# OpenBook_Schematic.net
KiCad netlist of a schematic drawn in EAGLE
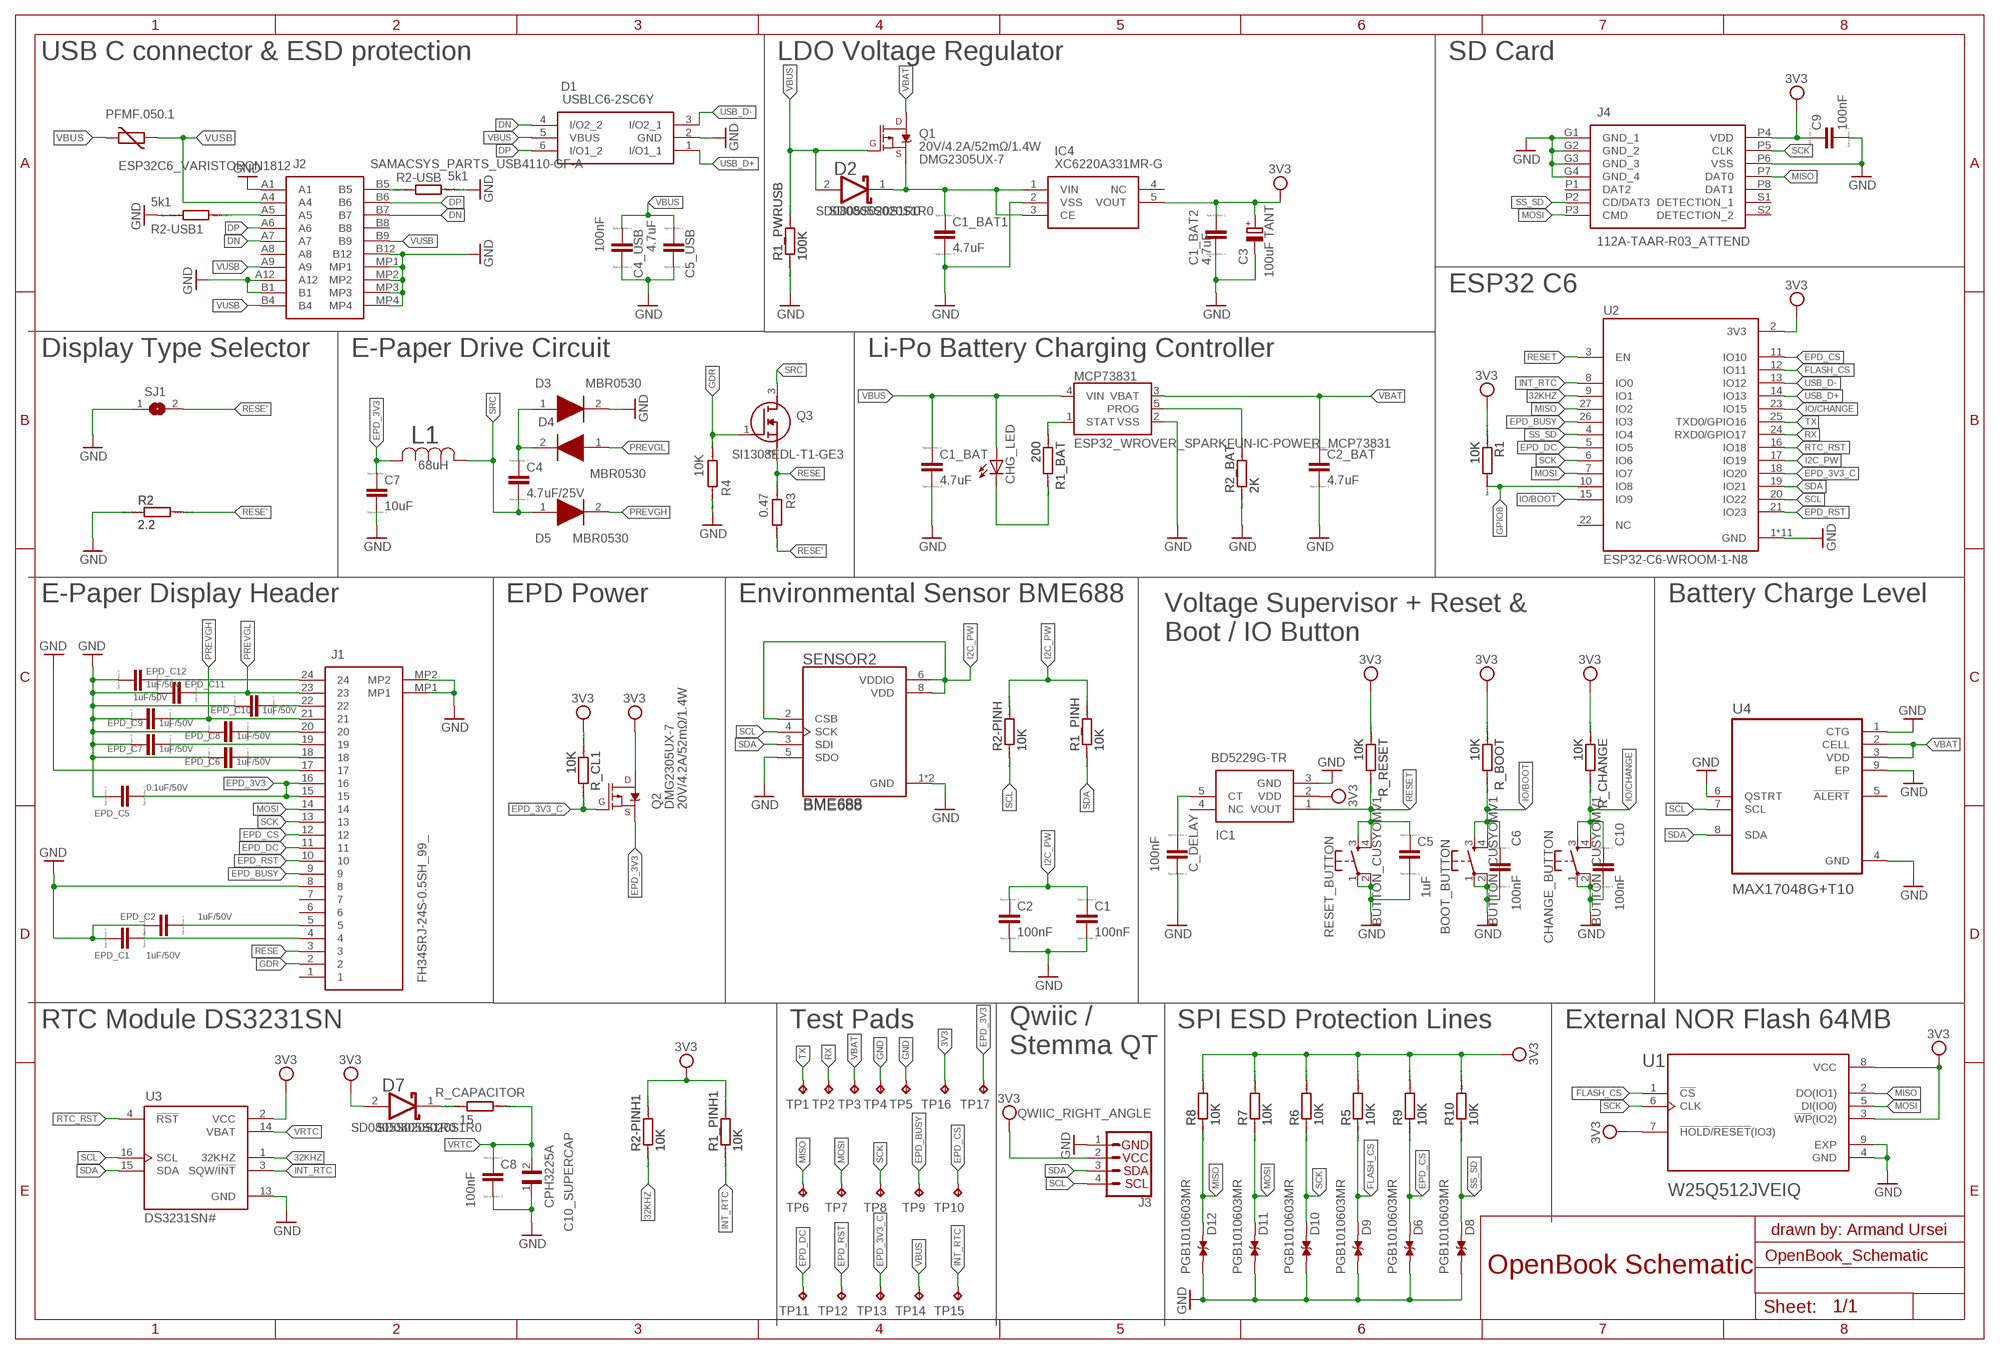
[diagram p0: schematic, sheet 1]

(export (version "E")
  (design (tool "Eeschema 10.0.6"))
  (components
    (comp (ref "BOOT_BUTTON")
      (value "BUTTON_CUSYOMV1")
      (footprint "eagle-import:MYBUTTON")
      (libsource (lib "eagle-import") (part "BUTTON_CUSYOMV1"))
    )
    (comp (ref "C1")
      (value "100nF")
      (footprint "eagle-import:ESP32_WROVER_EAGLE-LTSPICE_C0402")
      (libsource (lib "eagle-import") (part "ESP32_WROVER_EAGLE-LTSPICE_CC0402"))
    )
    (comp (ref "C1_BAT")
      (value "4.7uF")
      (footprint "eagle-import:ESP32_WROVER_EAGLE-LTSPICE_C0402")
      (libsource (lib "eagle-import") (part "ESP32_WROVER_EAGLE-LTSPICE_CC0402"))
    )
    (comp (ref "C1_BAT1")
      (value "4.7uF")
      (footprint "eagle-import:ESP32_WROVER_EAGLE-LTSPICE_C0402")
      (libsource (lib "eagle-import") (part "ESP32_WROVER_EAGLE-LTSPICE_CC0402"))
    )
    (comp (ref "C1_BAT2")
      (value "4.7uF")
      (footprint "eagle-import:ESP32_WROVER_EAGLE-LTSPICE_C0402")
      (libsource (lib "eagle-import") (part "ESP32_WROVER_EAGLE-LTSPICE_CC0402"))
    )
    (comp (ref "C2")
      (value "100nF")
      (footprint "eagle-import:ESP32_WROVER_EAGLE-LTSPICE_C0402")
      (libsource (lib "eagle-import") (part "ESP32_WROVER_EAGLE-LTSPICE_CC0402"))
    )
    (comp (ref "C2_BAT")
      (value "4.7uF")
      (footprint "eagle-import:ESP32_WROVER_EAGLE-LTSPICE_C0402")
      (libsource (lib "eagle-import") (part "ESP32_WROVER_EAGLE-LTSPICE_CC0402"))
    )
    (comp (ref "C3")
      (value "100uF TANT")
      (footprint "eagle-import:RCL_CT3528")
      (libsource (lib "eagle-import") (part "RCL_CPOL-EUCT3528"))
    )
    (comp (ref "C4")
      (value "4.7uF/25V")
      (footprint "eagle-import:ESP32_WROVER_EAGLE-LTSPICE_C0402")
      (libsource (lib "eagle-import") (part "ESP32_WROVER_EAGLE-LTSPICE_CC0402"))
    )
    (comp (ref "C4_USB")
      (value "100nF")
      (footprint "eagle-import:ESP32_WROVER_EAGLE-LTSPICE_C0402")
      (libsource (lib "eagle-import") (part "ESP32_WROVER_EAGLE-LTSPICE_CC0402"))
    )
    (comp (ref "C5")
      (value "1uF")
      (footprint "eagle-import:ESP32_WROVER_EAGLE-LTSPICE_C0402")
      (libsource (lib "eagle-import") (part "ESP32_WROVER_EAGLE-LTSPICE_CC0402"))
    )
    (comp (ref "C5_USB")
      (value "4.7uF")
      (footprint "eagle-import:ESP32_WROVER_EAGLE-LTSPICE_C0402")
      (libsource (lib "eagle-import") (part "ESP32_WROVER_EAGLE-LTSPICE_CC0402"))
    )
    (comp (ref "C6")
      (value "100nF")
      (footprint "eagle-import:ESP32_WROVER_EAGLE-LTSPICE_C0402")
      (libsource (lib "eagle-import") (part "ESP32_WROVER_EAGLE-LTSPICE_CC0402"))
    )
    (comp (ref "C7")
      (value "10uF")
      (footprint "eagle-import:ESP32_WROVER_EAGLE-LTSPICE_C0402")
      (libsource (lib "eagle-import") (part "ESP32_WROVER_EAGLE-LTSPICE_CC0402"))
    )
    (comp (ref "C8")
      (value "100nF")
      (footprint "eagle-import:ESP32_WROVER_EAGLE-LTSPICE_C0402")
      (libsource (lib "eagle-import") (part "ESP32_WROVER_EAGLE-LTSPICE_CC0402"))
    )
    (comp (ref "C9")
      (value "100nF")
      (footprint "eagle-import:ESP32_WROVER_EAGLE-LTSPICE_C0402")
      (libsource (lib "eagle-import") (part "ESP32_WROVER_EAGLE-LTSPICE_CC0402"))
    )
    (comp (ref "C10")
      (value "100nF")
      (footprint "eagle-import:ESP32_WROVER_EAGLE-LTSPICE_C0402")
      (libsource (lib "eagle-import") (part "ESP32_WROVER_EAGLE-LTSPICE_CC0402"))
    )
    (comp (ref "C10_SUPERCAP")
      (value "CPH3225A")
      (footprint "eagle-import:CAPCP3225X100N")
      (fields (field (name "MF") "Seiko Instruments"))
      (libsource (lib "eagle-import") (part "CPH3225A"))
    )
    (comp (ref "CHANGE_BUTTON")
      (value "BUTTON_CUSYOMV1")
      (footprint "eagle-import:MYBUTTON")
      (libsource (lib "eagle-import") (part "BUTTON_CUSYOMV1"))
    )
    (comp (ref "CHG_LED")
      (value "ADAFRUIT_LEDCHIP-LED0603")
      (footprint "eagle-import:ADAFRUIT_CHIP-LED0603")
      (libsource (lib "eagle-import") (part "ADAFRUIT_LEDCHIP-LED0603"))
    )
    (comp (ref "C_DELAY")
      (value "100nF")
      (footprint "eagle-import:ESP32_WROVER_EAGLE-LTSPICE_C0402")
      (libsource (lib "eagle-import") (part "ESP32_WROVER_EAGLE-LTSPICE_CC0402"))
    )
    (comp (ref "D1")
      (value "USBLC6-2SC6Y")
      (footprint "eagle-import:SOT95P280X145-6N")
      (fields (field (name "MF") "STMicroelectronics"))
      (libsource (lib "eagle-import") (part "USBLC6-2SC6Y"))
    )
    (comp (ref "D2")
      (value "SD0805S020S1R0")
      (footprint "eagle-import:ESP32_WROVER_AVX---SD0805S020S1R0_AVX_SD0805S020S1R0_0")
      (fields
        (field (name "DIGIKEY_PART_NUMBER") "478-7800-1-ND")
        (field (name "MF") "AVX")
        (field (name "MOUSER_PART_NUMBER") "581-SD0805S020S1R0")
      )
      (libsource (lib "eagle-import") (part "ESP32_WROVER_AVX---SD0805S020S1R0_AVX_SD0805S020S1R0_0_0AVX_SD0805S020S1R0_0_0"))
    )
    (comp (ref "D3")
      (value "MBR0530")
      (footprint "eagle-import:SOD3716X135N")
      (libsource (lib "eagle-import") (part "MBR0530"))
    )
    (comp (ref "D4")
      (value "MBR0530")
      (footprint "eagle-import:SOD3716X135N")
      (libsource (lib "eagle-import") (part "MBR0530"))
    )
    (comp (ref "D5")
      (value "MBR0530")
      (footprint "eagle-import:SOD3716X135N")
      (libsource (lib "eagle-import") (part "MBR0530"))
    )
    (comp (ref "D6")
      (value "PGB1010603MR")
      (footprint "eagle-import:DIOC1608X36N")
      (libsource (lib "eagle-import") (part "PGB1010603MR"))
    )
    (comp (ref "D7")
      (value "SD0805S020S1R0")
      (footprint "eagle-import:ESP32_WROVER_AVX---SD0805S020S1R0_AVX_SD0805S020S1R0_0")
      (fields
        (field (name "DIGIKEY_PART_NUMBER") "478-7800-1-ND")
        (field (name "MF") "AVX")
        (field (name "MOUSER_PART_NUMBER") "581-SD0805S020S1R0")
      )
      (libsource (lib "eagle-import") (part "ESP32_WROVER_AVX---SD0805S020S1R0_AVX_SD0805S020S1R0_0_0AVX_SD0805S020S1R0_0_0"))
    )
    (comp (ref "D8")
      (value "PGB1010603MR")
      (footprint "eagle-import:DIOC1608X36N")
      (libsource (lib "eagle-import") (part "PGB1010603MR"))
    )
    (comp (ref "D9")
      (value "PGB1010603MR")
      (footprint "eagle-import:DIOC1608X36N")
      (libsource (lib "eagle-import") (part "PGB1010603MR"))
    )
    (comp (ref "D10")
      (value "PGB1010603MR")
      (footprint "eagle-import:DIOC1608X36N")
      (libsource (lib "eagle-import") (part "PGB1010603MR"))
    )
    (comp (ref "D11")
      (value "PGB1010603MR")
      (footprint "eagle-import:DIOC1608X36N")
      (libsource (lib "eagle-import") (part "PGB1010603MR"))
    )
    (comp (ref "D12")
      (value "PGB1010603MR")
      (footprint "eagle-import:DIOC1608X36N")
      (libsource (lib "eagle-import") (part "PGB1010603MR"))
    )
    (comp (ref "EPD_C1")
      (value "1uF/50V")
      (footprint "eagle-import:ESP32_WROVER_EAGLE-LTSPICE_C0402")
      (libsource (lib "eagle-import") (part "ESP32_WROVER_EAGLE-LTSPICE_CC0402"))
    )
    (comp (ref "EPD_C2")
      (value "1uF/50V")
      (footprint "eagle-import:ESP32_WROVER_EAGLE-LTSPICE_C0402")
      (libsource (lib "eagle-import") (part "ESP32_WROVER_EAGLE-LTSPICE_CC0402"))
    )
    (comp (ref "EPD_C5")
      (value "0.1uF/50V")
      (footprint "eagle-import:ESP32_WROVER_EAGLE-LTSPICE_C0402")
      (libsource (lib "eagle-import") (part "ESP32_WROVER_EAGLE-LTSPICE_CC0402"))
    )
    (comp (ref "EPD_C6")
      (value "1uF/50V")
      (footprint "eagle-import:ESP32_WROVER_EAGLE-LTSPICE_C0402")
      (libsource (lib "eagle-import") (part "ESP32_WROVER_EAGLE-LTSPICE_CC0402"))
    )
    (comp (ref "EPD_C7")
      (value "1uF/50V")
      (footprint "eagle-import:ESP32_WROVER_EAGLE-LTSPICE_C0402")
      (libsource (lib "eagle-import") (part "ESP32_WROVER_EAGLE-LTSPICE_CC0402"))
    )
    (comp (ref "EPD_C8")
      (value "1uF/50V")
      (footprint "eagle-import:ESP32_WROVER_EAGLE-LTSPICE_C0402")
      (libsource (lib "eagle-import") (part "ESP32_WROVER_EAGLE-LTSPICE_CC0402"))
    )
    (comp (ref "EPD_C9")
      (value "1uF/50V")
      (footprint "eagle-import:ESP32_WROVER_EAGLE-LTSPICE_C0402")
      (libsource (lib "eagle-import") (part "ESP32_WROVER_EAGLE-LTSPICE_CC0402"))
    )
    (comp (ref "EPD_C10")
      (value "1uF/50V")
      (footprint "eagle-import:ESP32_WROVER_EAGLE-LTSPICE_C0402")
      (libsource (lib "eagle-import") (part "ESP32_WROVER_EAGLE-LTSPICE_CC0402"))
    )
    (comp (ref "EPD_C11")
      (value "1uF/50V")
      (footprint "eagle-import:ESP32_WROVER_EAGLE-LTSPICE_C0402")
      (libsource (lib "eagle-import") (part "ESP32_WROVER_EAGLE-LTSPICE_CC0402"))
    )
    (comp (ref "EPD_C12")
      (value "1uF/50V")
      (footprint "eagle-import:ESP32_WROVER_EAGLE-LTSPICE_C0402")
      (libsource (lib "eagle-import") (part "ESP32_WROVER_EAGLE-LTSPICE_CC0402"))
    )
    (comp (ref "IC1")
      (value "BD5229G-TR")
      (footprint "eagle-import:SOT95P280X125-5N")
      (fields (field (name "MOUSER_PART_NUMBER") "755-BD5229G-TR"))
      (libsource (lib "eagle-import") (part "BD5229G-TR"))
    )
    (comp (ref "IC4")
      (value "XC6220A331MR-G")
      (footprint "eagle-import:SOT95P280X120-5N")
      (fields (field (name "MOUSER_PART_NUMBER") "865-XC6220A331MR-G"))
      (libsource (lib "eagle-import") (part "XC6220A331MR-G"))
    )
    (comp (ref "J1")
      (value "FH34SRJ-24S-0.5SH_99_")
      (footprint "eagle-import:FH34SRJ24S05SH99")
      (fields
        (field (name "MANUFACTURER_PART_NUMBER") "FH34SRJ-24S-0.5SH(99)")
        (field (name "MOUSER_PART_NUMBER") "798-FH34SRJ24S05SH99")
      )
      (libsource (lib "eagle-import") (part "FH34SRJ-24S-0.5SH_99_"))
    )
    (comp (ref "J2")
      (value "SAMACSYS_PARTS_USB4110-GF-A")
      (footprint "eagle-import:SAMACSYS_PARTS_USB4110GFA")
      (fields
        (field (name "MANUFACTURER_PART_NUMBER") "USB4110-GF-A")
        (field (name "MOUSER_PART_NUMBER") "640-USB4110-GF-A")
      )
      (libsource (lib "eagle-import") (part "SAMACSYS_PARTS_USB4110-GF-A"))
    )
    (comp (ref "J3")
      (value "QWIIC_RIGHT_ANGLE")
      (footprint "eagle-import:JST04_1MM_RA")
      (libsource (lib "eagle-import") (part "QWIIC_CONNECTORJS-1MM"))
    )
    (comp (ref "J4")
      (value "112A-TAAR-R03_ATTEND")
      (footprint "eagle-import:112ATAARR03ATTEND")
      (fields (field (name "MANUFACTURER_PART_NUMBER") "112A-TAAR-R03 ATTEND"))
      (libsource (lib "eagle-import") (part "112A-TAAR-R03_ATTEND"))
    )
    (comp (ref "L1")
      (value "68uH")
      (footprint "eagle-import:IND_4828-WE-TPC_WRE")
      (fields
        (field (name "MANUFACTURER_PART_NUMBER") "744043680")
        (field (name "COPYRIGHT") "Copyright (C) 2024 Ultra Librarian. All rights reserved.")
      )
      (libsource (lib "eagle-import") (part "744043680IND_4828-WE-TPC_WRE"))
    )
    (comp (ref "MCP73831")
      (value "ESP32_WROVER_SPARKFUN-IC-POWER_MCP73831")
      (footprint "eagle-import:ESP32_WROVER_SPARKFUN-IC-POWER_SOT23-5")
      (libsource (lib "eagle-import") (part "ESP32_WROVER_SPARKFUN-IC-POWER_MCP73831"))
    )
    (comp (ref "PFMF.050.1")
      (value "ESP32C6_VARISTORCN1812")
      (footprint "eagle-import:ESP32C6_VARISTOR_CT_CN1812")
      (libsource (lib "eagle-import") (part "ESP32C6_VARISTORCN1812"))
    )
    (comp (ref "Q1")
      (value "20V/4.2A/52mΩ/1.4W")
      (footprint "eagle-import:ESP32_WROVER_SPARKFUN-DISCRETESEMI_SOT23-3")
      (libsource (lib "eagle-import") (part "ESP32_WROVER_SPARKFUN-DISCRETESEMI_MOSFET_PCH-DMG2305UX-7"))
    )
    (comp (ref "Q2")
      (value "20V/4.2A/52mΩ/1.4W")
      (footprint "eagle-import:ESP32_WROVER_SPARKFUN-DISCRETESEMI_SOT23-3")
      (libsource (lib "eagle-import") (part "ESP32_WROVER_SPARKFUN-DISCRETESEMI_MOSFET_PCH-DMG2305UX-7"))
    )
    (comp (ref "Q3")
      (value "SI1308EDL-T1-GE3")
      (footprint "eagle-import:SOT65P210X110-3N")
      (fields (field (name "MF") "Vishay Siliconix"))
      (libsource (lib "eagle-import") (part "SI1308EDL-T1-GE3"))
    )
    (comp (ref "R1")
      (value "10K")
      (footprint "eagle-import:ESP32_WROVER_EAGLE-LTSPICE_R0402")
      (libsource (lib "eagle-import") (part "ESP32_WROVER_EAGLE-LTSPICE_RR0402"))
    )
    (comp (ref "R1_BAT")
      (value "200")
      (footprint "eagle-import:ESP32_WROVER_EAGLE-LTSPICE_R0402")
      (libsource (lib "eagle-import") (part "ESP32_WROVER_EAGLE-LTSPICE_RR0402"))
    )
    (comp (ref "R1_PINH")
      (value "10K")
      (footprint "eagle-import:ESP32_WROVER_EAGLE-LTSPICE_R0402")
      (libsource (lib "eagle-import") (part "ESP32_WROVER_EAGLE-LTSPICE_RR0402"))
    )
    (comp (ref "R1_PINH1")
      (value "10K")
      (footprint "eagle-import:ESP32_WROVER_EAGLE-LTSPICE_R0402")
      (libsource (lib "eagle-import") (part "ESP32_WROVER_EAGLE-LTSPICE_RR0402"))
    )
    (comp (ref "R1_PWRUSB")
      (value "100K")
      (footprint "eagle-import:ESP32_WROVER_EAGLE-LTSPICE_R0402")
      (libsource (lib "eagle-import") (part "ESP32_WROVER_EAGLE-LTSPICE_RR0402"))
    )
    (comp (ref "R2")
      (value "2.2")
      (footprint "eagle-import:ESP32_WROVER_EAGLE-LTSPICE_R0402")
      (libsource (lib "eagle-import") (part "ESP32_WROVER_EAGLE-LTSPICE_RR0402"))
    )
    (comp (ref "R2-PINH")
      (value "10K")
      (footprint "eagle-import:ESP32_WROVER_EAGLE-LTSPICE_R0402")
      (libsource (lib "eagle-import") (part "ESP32_WROVER_EAGLE-LTSPICE_RR0402"))
    )
    (comp (ref "R2-PINH1")
      (value "10K")
      (footprint "eagle-import:ESP32_WROVER_EAGLE-LTSPICE_R0402")
      (libsource (lib "eagle-import") (part "ESP32_WROVER_EAGLE-LTSPICE_RR0402"))
    )
    (comp (ref "R2-USB")
      (value "5k1")
      (footprint "eagle-import:ESP32_WROVER_EAGLE-LTSPICE_R0402")
      (libsource (lib "eagle-import") (part "ESP32_WROVER_EAGLE-LTSPICE_RR0402"))
    )
    (comp (ref "R2-USB1")
      (value "5k1")
      (footprint "eagle-import:ESP32_WROVER_EAGLE-LTSPICE_R0402")
      (libsource (lib "eagle-import") (part "ESP32_WROVER_EAGLE-LTSPICE_RR0402"))
    )
    (comp (ref "R2_BAT")
      (value "2K")
      (footprint "eagle-import:ESP32_WROVER_EAGLE-LTSPICE_R0402")
      (libsource (lib "eagle-import") (part "ESP32_WROVER_EAGLE-LTSPICE_RR0402"))
    )
    (comp (ref "R3")
      (value "0.47")
      (footprint "eagle-import:ESP32_WROVER_EAGLE-LTSPICE_R0402")
      (libsource (lib "eagle-import") (part "ESP32_WROVER_EAGLE-LTSPICE_RR0402"))
    )
    (comp (ref "R4")
      (value "10K")
      (footprint "eagle-import:ESP32_WROVER_EAGLE-LTSPICE_R0402")
      (libsource (lib "eagle-import") (part "ESP32_WROVER_EAGLE-LTSPICE_RR0402"))
    )
    (comp (ref "R5")
      (value "10K")
      (footprint "eagle-import:ESP32_WROVER_EAGLE-LTSPICE_R0402")
      (libsource (lib "eagle-import") (part "ESP32_WROVER_EAGLE-LTSPICE_RR0402"))
    )
    (comp (ref "R6")
      (value "10K")
      (footprint "eagle-import:ESP32_WROVER_EAGLE-LTSPICE_R0402")
      (libsource (lib "eagle-import") (part "ESP32_WROVER_EAGLE-LTSPICE_RR0402"))
    )
    (comp (ref "R7")
      (value "10K")
      (footprint "eagle-import:ESP32_WROVER_EAGLE-LTSPICE_R0402")
      (libsource (lib "eagle-import") (part "ESP32_WROVER_EAGLE-LTSPICE_RR0402"))
    )
    (comp (ref "R8")
      (value "10K")
      (footprint "eagle-import:ESP32_WROVER_EAGLE-LTSPICE_R0402")
      (libsource (lib "eagle-import") (part "ESP32_WROVER_EAGLE-LTSPICE_RR0402"))
    )
    (comp (ref "R9")
      (value "10K")
      (footprint "eagle-import:ESP32_WROVER_EAGLE-LTSPICE_R0402")
      (libsource (lib "eagle-import") (part "ESP32_WROVER_EAGLE-LTSPICE_RR0402"))
    )
    (comp (ref "R10")
      (value "10K")
      (footprint "eagle-import:ESP32_WROVER_EAGLE-LTSPICE_R0402")
      (libsource (lib "eagle-import") (part "ESP32_WROVER_EAGLE-LTSPICE_RR0402"))
    )
    (comp (ref "RESET_BUTTON")
      (value "BUTTON_CUSYOMV1")
      (footprint "eagle-import:MYBUTTON")
      (libsource (lib "eagle-import") (part "BUTTON_CUSYOMV1"))
    )
    (comp (ref "R_BOOT")
      (value "10K")
      (footprint "eagle-import:ESP32_WROVER_EAGLE-LTSPICE_R0402")
      (libsource (lib "eagle-import") (part "ESP32_WROVER_EAGLE-LTSPICE_RR0402"))
    )
    (comp (ref "R_CAPACITOR")
      (value "15")
      (footprint "eagle-import:ESP32_WROVER_EAGLE-LTSPICE_R0402")
      (libsource (lib "eagle-import") (part "ESP32_WROVER_EAGLE-LTSPICE_RR0402"))
    )
    (comp (ref "R_CHANGE")
      (value "10K")
      (footprint "eagle-import:ESP32_WROVER_EAGLE-LTSPICE_R0402")
      (libsource (lib "eagle-import") (part "ESP32_WROVER_EAGLE-LTSPICE_RR0402"))
    )
    (comp (ref "R_CL1")
      (value "10K")
      (footprint "eagle-import:ESP32_WROVER_EAGLE-LTSPICE_R0402")
      (libsource (lib "eagle-import") (part "ESP32_WROVER_EAGLE-LTSPICE_RR0402"))
    )
    (comp (ref "R_RESET")
      (value "10K")
      (footprint "eagle-import:ESP32_WROVER_EAGLE-LTSPICE_R0402")
      (libsource (lib "eagle-import") (part "ESP32_WROVER_EAGLE-LTSPICE_RR0402"))
    )
    (comp (ref "SENSOR2")
      (value "BME688")
      (footprint "eagle-import:ESP32_WROVER_BME680_PSON80P300X300X100-8N")
      (fields (field (name "MF") "Bosch Sensortec") (field (name "MP") "BME680"))
      (libsource (lib "eagle-import") (part "ESP32_WROVER_BME680_BME680"))
    )
    (comp (ref "SJ1") (value "SJ") (footprint "eagle-import:SJ") (libsource (lib "eagle-import") (part "SJ")))
    (comp (ref "TP1")
      (value "TPTP20R")
      (footprint "eagle-import:TP20R")
      (libsource (lib "eagle-import") (part "TPTP20R"))
    )
    (comp (ref "TP2")
      (value "TPTP20R")
      (footprint "eagle-import:TP20R")
      (libsource (lib "eagle-import") (part "TPTP20R"))
    )
    (comp (ref "TP3")
      (value "TPTP20R")
      (footprint "eagle-import:TP20R")
      (libsource (lib "eagle-import") (part "TPTP20R"))
    )
    (comp (ref "TP4")
      (value "TPTP20R")
      (footprint "eagle-import:TP20R")
      (libsource (lib "eagle-import") (part "TPTP20R"))
    )
    (comp (ref "TP5")
      (value "TPTP20R")
      (footprint "eagle-import:TP20R")
      (libsource (lib "eagle-import") (part "TPTP20R"))
    )
    (comp (ref "TP6")
      (value "TPTP20R")
      (footprint "eagle-import:TP20R")
      (libsource (lib "eagle-import") (part "TPTP20R"))
    )
    (comp (ref "TP7")
      (value "TPTP20R")
      (footprint "eagle-import:TP20R")
      (libsource (lib "eagle-import") (part "TPTP20R"))
    )
    (comp (ref "TP8")
      (value "TPTP20R")
      (footprint "eagle-import:TP20R")
      (libsource (lib "eagle-import") (part "TPTP20R"))
    )
    (comp (ref "TP9")
      (value "TPTP20R")
      (footprint "eagle-import:TP20R")
      (libsource (lib "eagle-import") (part "TPTP20R"))
    )
    (comp (ref "TP10")
      (value "TPTP20R")
      (footprint "eagle-import:TP20R")
      (libsource (lib "eagle-import") (part "TPTP20R"))
    )
    (comp (ref "TP11")
      (value "TPTP20R")
      (footprint "eagle-import:TP20R")
      (libsource (lib "eagle-import") (part "TPTP20R"))
    )
    (comp (ref "TP12")
      (value "TPTP20R")
      (footprint "eagle-import:TP20R")
      (libsource (lib "eagle-import") (part "TPTP20R"))
    )
    (comp (ref "TP13")
      (value "TPTP20R")
      (footprint "eagle-import:TP20R")
      (libsource (lib "eagle-import") (part "TPTP20R"))
    )
    (comp (ref "TP14")
      (value "TPTP20R")
      (footprint "eagle-import:TP20R")
      (libsource (lib "eagle-import") (part "TPTP20R"))
    )
    (comp (ref "TP15")
      (value "TPTP20R")
      (footprint "eagle-import:TP20R")
      (libsource (lib "eagle-import") (part "TPTP20R"))
    )
    (comp (ref "TP16")
      (value "TPTP20R")
      (footprint "eagle-import:TP20R")
      (libsource (lib "eagle-import") (part "TPTP20R"))
    )
    (comp (ref "TP17")
      (value "TPTP20R")
      (footprint "eagle-import:TP20R")
      (libsource (lib "eagle-import") (part "TPTP20R"))
    )
    (comp (ref "U1")
      (value "W25Q512JVEIQ")
      (footprint "eagle-import:SON127P600X800X80-9N")
      (fields (field (name "MF") "Winbond Electronics"))
      (libsource (lib "eagle-import") (part "W25Q512JVEIQ"))
    )
    (comp (ref "U2")
      (value "ESP32-C6-WROOM-1-N8")
      (footprint "eagle-import:XCVR_ESP32-C6-WROOM-1-N8")
      (fields (field (name "MF") "Espressif Systems"))
      (libsource (lib "eagle-import") (part "ESP32-C6-WROOM-1-N8"))
    )
    (comp (ref "U3")
      (value "DS3231SN#")
      (footprint "eagle-import:SOIC127P1032X265-16N")
      (fields (field (name "MF") "Analog Devices"))
      (libsource (lib "eagle-import") (part "DS3231SN#"))
    )
    (comp (ref "U4")
      (value "MAX17048G+T10")
      (footprint "eagle-import:SON50P200X200X80-9N")
      (fields (field (name "MF") "Analog Devices"))
      (libsource (lib "eagle-import") (part "MAX17048G+T10"))
    )
  )
  (nets
    (net (code "1") (name "3V3") (class "Default")
      (node (ref "C1_BAT2") (pin "1") (pinfunction "1_1") (pintype "passive"))
      (node (ref "C3") (pin "+") (pinfunction "+_+") (pintype "passive"))
      (node (ref "C9") (pin "1") (pinfunction "1_1") (pintype "passive"))
      (node (ref "D7") (pin "2") (pinfunction "ANODE_2") (pintype "bidirectional"))
      (node (ref "IC1") (pin "2") (pinfunction "VDD_2") (pintype "bidirectional"))
      (node (ref "IC4") (pin "5") (pinfunction "VOUT_5") (pintype "bidirectional"))
      (node (ref "J3") (pin "2") (pinfunction "2_2") (pintype "power_in"))
      (node (ref "J4") (pin "P4") (pinfunction "VDD_P4") (pintype "bidirectional"))
      (node (ref "Q2") (pin "3") (pinfunction "D_3") (pintype "bidirectional"))
      (node (ref "R1") (pin "1") (pinfunction "1_1") (pintype "passive"))
      (node (ref "R10") (pin "2") (pinfunction "2_2") (pintype "passive"))
      (node (ref "R1_PINH1") (pin "2") (pinfunction "2_2") (pintype "passive"))
      (node (ref "R2-PINH1") (pin "2") (pinfunction "2_2") (pintype "passive"))
      (node (ref "R5") (pin "2") (pinfunction "2_2") (pintype "passive"))
      (node (ref "R6") (pin "2") (pinfunction "2_2") (pintype "passive"))
      (node (ref "R7") (pin "2") (pinfunction "2_2") (pintype "passive"))
      (node (ref "R8") (pin "2") (pinfunction "2_2") (pintype "passive"))
      (node (ref "R9") (pin "2") (pinfunction "2_2") (pintype "passive"))
      (node (ref "R_BOOT") (pin "1") (pinfunction "1_1") (pintype "passive"))
      (node (ref "R_CHANGE") (pin "1") (pinfunction "1_1") (pintype "passive"))
      (node (ref "R_CL1") (pin "1") (pinfunction "1_1") (pintype "passive"))
      (node (ref "R_RESET") (pin "1") (pinfunction "1_1") (pintype "passive"))
      (node (ref "TP16") (pin "TP") (pinfunction "TP_TP") (pintype "input"))
      (node (ref "U1") (pin "3") (pinfunction "~{WP}(IO2)_3") (pintype "bidirectional"))
      (node (ref "U1") (pin "7") (pinfunction "~{HOLD}/~{RESET}(IO3)_7") (pintype "bidirectional"))
      (node (ref "U1") (pin "8") (pinfunction "VCC_8") (pintype "power_in"))
      (node (ref "U2") (pin "2") (pinfunction "3V3_2") (pintype "power_in"))
      (node (ref "U3") (pin "2") (pinfunction "VCC_2") (pintype "power_in"))
    )
    (net (code "2") (name "32KHZ") (class "Default")
      (node (ref "R2-PINH1") (pin "1") (pinfunction "1_1") (pintype "passive"))
      (node (ref "U2") (pin "9") (pinfunction "IO1_9") (pintype "bidirectional"))
      (node (ref "U3") (pin "1") (pinfunction "32KHZ_1") (pintype "output"))
    )
    (net (code "3") (name "DN") (class "Default")
      (node (ref "D1") (pin "4") (pinfunction "I/O2_2_4") (pintype "bidirectional"))
      (node (ref "J2") (pin "A7") (pinfunction "A7_A7") (pintype "bidirectional"))
      (node (ref "J2") (pin "B7") (pinfunction "B7_B7") (pintype "bidirectional"))
    )
    (net (code "4") (name "DP") (class "Default")
      (node (ref "D1") (pin "6") (pinfunction "I/O1_2_6") (pintype "bidirectional"))
      (node (ref "J2") (pin "A6") (pinfunction "A6_A6") (pintype "bidirectional"))
      (node (ref "J2") (pin "B6") (pinfunction "B6_B6") (pintype "bidirectional"))
    )
    (net (code "5") (name "EPD_3V3") (class "Default")
      (node (ref "C7") (pin "1") (pinfunction "1_1") (pintype "passive"))
      (node (ref "EPD_C5") (pin "1") (pinfunction "1_1") (pintype "passive"))
      (node (ref "J1") (pin "15") (pinfunction "15_15") (pintype "bidirectional"))
      (node (ref "J1") (pin "16") (pinfunction "16_16") (pintype "bidirectional"))
      (node (ref "L1") (pin "2") (pinfunction "2_2") (pintype "passive"))
      (node (ref "Q2") (pin "2") (pinfunction "S_2") (pintype "bidirectional"))
      (node (ref "TP17") (pin "TP") (pinfunction "TP_TP") (pintype "input"))
    )
    (net (code "6") (name "EPD_3V3_C") (class "Default")
      (node (ref "Q2") (pin "1") (pinfunction "G_1") (pintype "bidirectional"))
      (node (ref "R_CL1") (pin "2") (pinfunction "2_2") (pintype "passive"))
      (node (ref "TP13") (pin "TP") (pinfunction "TP_TP") (pintype "input"))
      (node (ref "U2") (pin "18") (pinfunction "IO20_18") (pintype "bidirectional"))
    )
    (net (code "7") (name "EPD_BUSY") (class "Default")
      (node (ref "J1") (pin "9") (pinfunction "9_9") (pintype "bidirectional"))
      (node (ref "TP9") (pin "TP") (pinfunction "TP_TP") (pintype "input"))
      (node (ref "U2") (pin "26") (pinfunction "IO3_26") (pintype "bidirectional"))
    )
    (net (code "8") (name "EPD_CS") (class "Default")
      (node (ref "D6") (pin "2") (pinfunction "2_2") (pintype "passive"))
      (node (ref "J1") (pin "12") (pinfunction "12_12") (pintype "bidirectional"))
      (node (ref "R9") (pin "1") (pinfunction "1_1") (pintype "passive"))
      (node (ref "TP10") (pin "TP") (pinfunction "TP_TP") (pintype "input"))
      (node (ref "U2") (pin "11") (pinfunction "IO10_11") (pintype "bidirectional"))
    )
    (net (code "9") (name "EPD_DC") (class "Default")
      (node (ref "J1") (pin "11") (pinfunction "11_11") (pintype "bidirectional"))
      (node (ref "TP11") (pin "TP") (pinfunction "TP_TP") (pintype "input"))
      (node (ref "U2") (pin "5") (pinfunction "IO5_5") (pintype "bidirectional"))
    )
    (net (code "10") (name "EPD_RST") (class "Default")
      (node (ref "J1") (pin "10") (pinfunction "10_10") (pintype "bidirectional"))
      (node (ref "TP12") (pin "TP") (pinfunction "TP_TP") (pintype "input"))
      (node (ref "U2") (pin "21") (pinfunction "IO23_21") (pintype "bidirectional"))
    )
    (net (code "11") (name "FLASH_CS") (class "Default")
      (node (ref "D9") (pin "2") (pinfunction "2_2") (pintype "passive"))
      (node (ref "R5") (pin "1") (pinfunction "1_1") (pintype "passive"))
      (node (ref "U1") (pin "1") (pinfunction "~{CS}_1") (pintype "input"))
      (node (ref "U2") (pin "12") (pinfunction "IO11_12") (pintype "bidirectional"))
    )
    (net (code "12") (name "GDR") (class "Default")
      (node (ref "J1") (pin "2") (pinfunction "2_2") (pintype "bidirectional"))
      (node (ref "Q3") (pin "1") (pinfunction "G_1") (pintype "bidirectional"))
      (node (ref "R4") (pin "1") (pinfunction "1_1") (pintype "passive"))
    )
    (net (code "13") (name "GND") (class "Default")
      (node (ref "BOOT_BUTTON") (pin "1") (pinfunction "1_1") (pintype "passive"))
      (node (ref "BOOT_BUTTON") (pin "2") (pinfunction "2_2") (pintype "passive"))
      (node (ref "C1") (pin "2") (pinfunction "2_2") (pintype "passive"))
      (node (ref "C10") (pin "2") (pinfunction "2_2") (pintype "passive"))
      (node (ref "C10_SUPERCAP") (pin "1") (pinfunction "1_1") (pintype "passive"))
      (node (ref "C1_BAT") (pin "2") (pinfunction "2_2") (pintype "passive"))
      (node (ref "C1_BAT1") (pin "2") (pinfunction "2_2") (pintype "passive"))
      (node (ref "C1_BAT2") (pin "2") (pinfunction "2_2") (pintype "passive"))
      (node (ref "C2") (pin "2") (pinfunction "2_2") (pintype "passive"))
      (node (ref "C2_BAT") (pin "2") (pinfunction "2_2") (pintype "passive"))
      (node (ref "C3") (pin "-") (pinfunction "-_-") (pintype "passive"))
      (node (ref "C4_USB") (pin "2") (pinfunction "2_2") (pintype "passive"))
      (node (ref "C5") (pin "2") (pinfunction "2_2") (pintype "passive"))
      (node (ref "C5_USB") (pin "2") (pinfunction "2_2") (pintype "passive"))
      (node (ref "C6") (pin "2") (pinfunction "2_2") (pintype "passive"))
      (node (ref "C7") (pin "2") (pinfunction "2_2") (pintype "passive"))
      (node (ref "C8") (pin "2") (pinfunction "2_2") (pintype "passive"))
      (node (ref "C9") (pin "2") (pinfunction "2_2") (pintype "passive"))
      (node (ref "CHANGE_BUTTON") (pin "1") (pinfunction "1_1") (pintype "passive"))
      (node (ref "CHANGE_BUTTON") (pin "2") (pinfunction "2_2") (pintype "passive"))
      (node (ref "C_DELAY") (pin "2") (pinfunction "2_2") (pintype "passive"))
      (node (ref "D1") (pin "2") (pinfunction "GND_2") (pintype "bidirectional"))
      (node (ref "D10") (pin "1") (pinfunction "1_1") (pintype "passive"))
      (node (ref "D11") (pin "1") (pinfunction "1_1") (pintype "passive"))
      (node (ref "D12") (pin "1") (pinfunction "1_1") (pintype "passive"))
      (node (ref "D3") (pin "2") (pinfunction "K_2") (pintype "bidirectional"))
      (node (ref "D6") (pin "1") (pinfunction "1_1") (pintype "passive"))
      (node (ref "D8") (pin "1") (pinfunction "1_1") (pintype "passive"))
      (node (ref "D9") (pin "1") (pinfunction "1_1") (pintype "passive"))
      (node (ref "EPD_C1") (pin "2") (pinfunction "2_2") (pintype "passive"))
      (node (ref "EPD_C10") (pin "2") (pinfunction "2_2") (pintype "passive"))
      (node (ref "EPD_C11") (pin "2") (pinfunction "2_2") (pintype "passive"))
      (node (ref "EPD_C12") (pin "2") (pinfunction "2_2") (pintype "passive"))
      (node (ref "EPD_C2") (pin "2") (pinfunction "2_2") (pintype "passive"))
      (node (ref "EPD_C5") (pin "2") (pinfunction "2_2") (pintype "passive"))
      (node (ref "EPD_C6") (pin "2") (pinfunction "2_2") (pintype "passive"))
      (node (ref "EPD_C7") (pin "2") (pinfunction "2_2") (pintype "passive"))
      (node (ref "EPD_C8") (pin "2") (pinfunction "2_2") (pintype "passive"))
      (node (ref "EPD_C9") (pin "2") (pinfunction "2_2") (pintype "passive"))
      (node (ref "IC1") (pin "3") (pinfunction "GND_3") (pintype "bidirectional"))
      (node (ref "IC4") (pin "2") (pinfunction "VSS_2") (pintype "bidirectional"))
      (node (ref "J1") (pin "17") (pinfunction "17_17") (pintype "bidirectional"))
      (node (ref "J1") (pin "8") (pinfunction "8_8") (pintype "bidirectional"))
      (node (ref "J1") (pin "MP1") (pinfunction "MP1_MP1") (pintype "bidirectional"))
      (node (ref "J1") (pin "MP2") (pinfunction "MP2_MP2") (pintype "bidirectional"))
      (node (ref "J2") (pin "A1") (pinfunction "A1_A1") (pintype "bidirectional"))
      (node (ref "J2") (pin "A12") (pinfunction "A12_A12") (pintype "bidirectional"))
      (node (ref "J2") (pin "B1") (pinfunction "B1_B1") (pintype "bidirectional"))
      (node (ref "J2") (pin "B12") (pinfunction "B12_B12") (pintype "bidirectional"))
      (node (ref "J2") (pin "MP1") (pinfunction "MP1_MP1") (pintype "bidirectional"))
      (node (ref "J2") (pin "MP2") (pinfunction "MP2_MP2") (pintype "bidirectional"))
      (node (ref "J2") (pin "MP3") (pinfunction "MP3_MP3") (pintype "bidirectional"))
      (node (ref "J2") (pin "MP4") (pinfunction "MP4_MP4") (pintype "bidirectional"))
      (node (ref "J3") (pin "1") (pinfunction "1_1") (pintype "power_in"))
      (node (ref "J4") (pin "G1") (pinfunction "GND_1_G1") (pintype "bidirectional"))
      (node (ref "J4") (pin "G2") (pinfunction "GND_2_G2") (pintype "bidirectional"))
      (node (ref "J4") (pin "G3") (pinfunction "GND_3_G3") (pintype "bidirectional"))
      (node (ref "J4") (pin "G4") (pinfunction "GND_4_G4") (pintype "bidirectional"))
      (node (ref "J4") (pin "P6") (pinfunction "VSS_P6") (pintype "bidirectional"))
      (node (ref "MCP73831") (pin "2") (pinfunction "VSS_2") (pintype "power_in"))
      (node (ref "R1_PWRUSB") (pin "1") (pinfunction "1_1") (pintype "passive"))
      (node (ref "R2") (pin "1") (pinfunction "1_1") (pintype "passive"))
      (node (ref "R2-USB") (pin "2") (pinfunction "2_2") (pintype "passive"))
      (node (ref "R2-USB1") (pin "1") (pinfunction "1_1") (pintype "passive"))
      (node (ref "R2_BAT") (pin "1") (pinfunction "1_1") (pintype "passive"))
      (node (ref "R4") (pin "2") (pinfunction "2_2") (pintype "passive"))
      (node (ref "RESET_BUTTON") (pin "1") (pinfunction "1_1") (pintype "passive"))
      (node (ref "RESET_BUTTON") (pin "2") (pinfunction "2_2") (pintype "passive"))
      (node (ref "SENSOR2") (pin "1") (pinfunction "GND_1") (pintype "power_in"))
      (node (ref "SENSOR2") (pin "5") (pinfunction "SDO_5") (pintype "bidirectional"))
      (node (ref "SENSOR2") (pin "7") (pinfunction "GND_7") (pintype "power_in"))
      (node (ref "SJ1") (pin "1") (pinfunction "1_1") (pintype "passive"))
      (node (ref "TP4") (pin "TP") (pinfunction "TP_TP") (pintype "input"))
      (node (ref "TP5") (pin "TP") (pinfunction "TP_TP") (pintype "input"))
      (node (ref "U1") (pin "4") (pinfunction "GND_4") (pintype "power_in"))
      (node (ref "U1") (pin "9") (pinfunction "EXP_9") (pintype "passive"))
      (node (ref "U2") (pin "1") (pinfunction "GND_1") (pintype "power_in"))
      (node (ref "U2") (pin "28") (pinfunction "GND_28") (pintype "power_in"))
      (node (ref "U2") (pin "29_1") (pinfunction "GND_29_1") (pintype "power_in"))
      (node (ref "U2") (pin "29_2") (pinfunction "GND_29_2") (pintype "power_in"))
      (node (ref "U2") (pin "29_3") (pinfunction "GND_29_3") (pintype "power_in"))
      (node (ref "U2") (pin "29_4") (pinfunction "GND_29_4") (pintype "power_in"))
      (node (ref "U2") (pin "29_5") (pinfunction "GND_29_5") (pintype "power_in"))
      (node (ref "U2") (pin "29_6") (pinfunction "GND_29_6") (pintype "power_in"))
      (node (ref "U2") (pin "29_7") (pinfunction "GND_29_7") (pintype "power_in"))
      (node (ref "U2") (pin "29_8") (pinfunction "GND_29_8") (pintype "power_in"))
      (node (ref "U2") (pin "29_9") (pinfunction "GND_29_9") (pintype "power_in"))
      (node (ref "U3") (pin "13") (pinfunction "GND_13") (pintype "power_in"))
      (node (ref "U4") (pin "1") (pinfunction "CTG_1") (pintype "power_in"))
      (node (ref "U4") (pin "4") (pinfunction "GND_4") (pintype "power_in"))
      (node (ref "U4") (pin "6") (pinfunction "QSTRT_6") (pintype "input"))
      (node (ref "U4") (pin "9") (pinfunction "EP_9") (pintype "power_in"))
    )
    (net (code "14") (name "GPIO8") (class "Default")
      (node (ref "R1") (pin "2") (pinfunction "2_2") (pintype "passive"))
      (node (ref "U2") (pin "10") (pinfunction "IO8_10") (pintype "bidirectional"))
    )
    (net (code "15") (name "I2C_PW") (class "Default")
      (node (ref "C1") (pin "1") (pinfunction "1_1") (pintype "passive"))
      (node (ref "C2") (pin "1") (pinfunction "1_1") (pintype "passive"))
      (node (ref "R1_PINH") (pin "2") (pinfunction "2_2") (pintype "passive"))
      (node (ref "R2-PINH") (pin "2") (pinfunction "2_2") (pintype "passive"))
      (node (ref "SENSOR2") (pin "2") (pinfunction "CSB_2") (pintype "input"))
      (node (ref "SENSOR2") (pin "6") (pinfunction "VDDIO_6") (pintype "power_in"))
      (node (ref "SENSOR2") (pin "8") (pinfunction "VDD_8") (pintype "power_in"))
      (node (ref "U2") (pin "17") (pinfunction "IO19_17") (pintype "bidirectional"))
    )
    (net (code "16") (name "INT_RTC") (class "Default")
      (node (ref "R1_PINH1") (pin "1") (pinfunction "1_1") (pintype "passive"))
      (node (ref "TP15") (pin "TP") (pinfunction "TP_TP") (pintype "input"))
      (node (ref "U2") (pin "8") (pinfunction "IO0_8") (pintype "bidirectional"))
      (node (ref "U3") (pin "3") (pinfunction "SQW/~{INT}_3") (pintype "output"))
    )
    (net (code "17") (name "IO{slash}BOOT") (class "Default")
      (node (ref "BOOT_BUTTON") (pin "3") (pinfunction "3_3") (pintype "passive"))
      (node (ref "BOOT_BUTTON") (pin "4") (pinfunction "4_4") (pintype "passive"))
      (node (ref "C6") (pin "1") (pinfunction "1_1") (pintype "passive"))
      (node (ref "R_BOOT") (pin "2") (pinfunction "2_2") (pintype "passive"))
      (node (ref "U2") (pin "15") (pinfunction "IO9_15") (pintype "bidirectional"))
    )
    (net (code "18") (name "IO{slash}CHANGE") (class "Default")
      (node (ref "C10") (pin "1") (pinfunction "1_1") (pintype "passive"))
      (node (ref "CHANGE_BUTTON") (pin "3") (pinfunction "3_3") (pintype "passive"))
      (node (ref "CHANGE_BUTTON") (pin "4") (pinfunction "4_4") (pintype "passive"))
      (node (ref "R_CHANGE") (pin "2") (pinfunction "2_2") (pintype "passive"))
      (node (ref "U2") (pin "23") (pinfunction "IO15_23") (pintype "bidirectional"))
    )
    (net (code "19") (name "MISO") (class "Default")
      (node (ref "D12") (pin "2") (pinfunction "2_2") (pintype "passive"))
      (node (ref "J4") (pin "P7") (pinfunction "DAT0_P7") (pintype "bidirectional"))
      (node (ref "R8") (pin "1") (pinfunction "1_1") (pintype "passive"))
      (node (ref "TP6") (pin "TP") (pinfunction "TP_TP") (pintype "input"))
      (node (ref "U1") (pin "2") (pinfunction "DO(IO1)_2") (pintype "bidirectional"))
      (node (ref "U2") (pin "27") (pinfunction "IO2_27") (pintype "bidirectional"))
    )
    (net (code "20") (name "MOSI") (class "Default")
      (node (ref "D11") (pin "2") (pinfunction "2_2") (pintype "passive"))
      (node (ref "J1") (pin "14") (pinfunction "14_14") (pintype "bidirectional"))
      (node (ref "J4") (pin "P3") (pinfunction "CMD_P3") (pintype "bidirectional"))
      (node (ref "R7") (pin "1") (pinfunction "1_1") (pintype "passive"))
      (node (ref "TP7") (pin "TP") (pinfunction "TP_TP") (pintype "input"))
      (node (ref "U1") (pin "5") (pinfunction "DI(IO0)_5") (pintype "bidirectional"))
      (node (ref "U2") (pin "7") (pinfunction "IO7_7") (pintype "bidirectional"))
    )
    (net (code "21") (name "Net-(CHG_LED-PadC)") (class "Default")
      (node (ref "CHG_LED") (pin "C") (pinfunction "C_C") (pintype "passive"))
      (node (ref "R1_BAT") (pin "2") (pinfunction "2_2") (pintype "passive"))
    )
    (net (code "22") (name "Net-(D2-CATHODE)") (class "Default")
      (node (ref "C1_BAT1") (pin "1") (pinfunction "1_1") (pintype "passive"))
      (node (ref "D2") (pin "1") (pinfunction "CATHODE_1") (pintype "bidirectional"))
      (node (ref "IC4") (pin "1") (pinfunction "VIN_1") (pintype "bidirectional"))
      (node (ref "IC4") (pin "3") (pinfunction "CE_3") (pintype "bidirectional"))
      (node (ref "Q1") (pin "2") (pinfunction "S_2") (pintype "bidirectional"))
    )
    (net (code "23") (name "Net-(D3-A)") (class "Default")
      (node (ref "C4") (pin "1") (pinfunction "1_1") (pintype "passive"))
      (node (ref "D3") (pin "1") (pinfunction "A_1") (pintype "bidirectional"))
      (node (ref "D4") (pin "2") (pinfunction "K_2") (pintype "bidirectional"))
    )
    (net (code "24") (name "Net-(D7-CATHODE)") (class "Default")
      (node (ref "D7") (pin "1") (pinfunction "CATHODE_1") (pintype "bidirectional"))
      (node (ref "R_CAPACITOR") (pin "2") (pinfunction "2_2") (pintype "passive"))
    )
    (net (code "25") (name "Net-(EPD_C1-Pad1)") (class "Default")
      (node (ref "EPD_C1") (pin "1") (pinfunction "1_1") (pintype "passive"))
      (node (ref "J1") (pin "4") (pinfunction "4_4") (pintype "bidirectional"))
    )
    (net (code "26") (name "Net-(EPD_C2-Pad1)") (class "Default")
      (node (ref "EPD_C2") (pin "1") (pinfunction "1_1") (pintype "passive"))
      (node (ref "J1") (pin "5") (pinfunction "5_5") (pintype "bidirectional"))
    )
    (net (code "27") (name "Net-(EPD_C6-Pad1)") (class "Default")
      (node (ref "EPD_C6") (pin "1") (pinfunction "1_1") (pintype "passive"))
      (node (ref "J1") (pin "18") (pinfunction "18_18") (pintype "bidirectional"))
    )
    (net (code "28") (name "Net-(EPD_C7-Pad1)") (class "Default")
      (node (ref "EPD_C7") (pin "1") (pinfunction "1_1") (pintype "passive"))
      (node (ref "J1") (pin "19") (pinfunction "19_19") (pintype "bidirectional"))
    )
    (net (code "29") (name "Net-(EPD_C8-Pad1)") (class "Default")
      (node (ref "EPD_C8") (pin "1") (pinfunction "1_1") (pintype "passive"))
      (node (ref "J1") (pin "20") (pinfunction "20_20") (pintype "bidirectional"))
    )
    (net (code "30") (name "Net-(EPD_C10-Pad1)") (class "Default")
      (node (ref "EPD_C10") (pin "1") (pinfunction "1_1") (pintype "passive"))
      (node (ref "J1") (pin "22") (pinfunction "22_22") (pintype "bidirectional"))
    )
    (net (code "31") (name "Net-(EPD_C12-Pad1)") (class "Default")
      (node (ref "EPD_C12") (pin "1") (pinfunction "1_1") (pintype "passive"))
      (node (ref "J1") (pin "24") (pinfunction "24_24") (pintype "bidirectional"))
    )
    (net (code "32") (name "Net-(IC1-CT)") (class "Default")
      (node (ref "C_DELAY") (pin "1") (pinfunction "1_1") (pintype "passive"))
      (node (ref "IC1") (pin "5") (pinfunction "CT_5") (pintype "bidirectional"))
    )
    (net (code "33") (name "Net-(J2-PadA5)") (class "Default")
      (node (ref "J2") (pin "A5") (pinfunction "A5_A5") (pintype "bidirectional"))
      (node (ref "R2-USB1") (pin "2") (pinfunction "2_2") (pintype "passive"))
    )
    (net (code "34") (name "Net-(J2-PadB5)") (class "Default")
      (node (ref "J2") (pin "B5") (pinfunction "B5_B5") (pintype "bidirectional"))
      (node (ref "R2-USB") (pin "1") (pinfunction "1_1") (pintype "passive"))
    )
    (net (code "35") (name "Net-(MCP73831-PROG)") (class "Default")
      (node (ref "MCP73831") (pin "5") (pinfunction "PROG_5") (pintype "input"))
      (node (ref "R2_BAT") (pin "2") (pinfunction "2_2") (pintype "passive"))
    )
    (net (code "36") (name "Net-(MCP73831-STAT)") (class "Default")
      (node (ref "MCP73831") (pin "1") (pinfunction "STAT_1") (pintype "output"))
      (node (ref "R1_BAT") (pin "1") (pinfunction "1_1") (pintype "passive"))
    )
    (net (code "37") (name "PREVGH") (class "Default")
      (node (ref "D5") (pin "2") (pinfunction "K_2") (pintype "bidirectional"))
      (node (ref "EPD_C9") (pin "1") (pinfunction "1_1") (pintype "passive"))
      (node (ref "J1") (pin "21") (pinfunction "21_21") (pintype "bidirectional"))
    )
    (net (code "38") (name "PREVGL") (class "Default")
      (node (ref "D4") (pin "1") (pinfunction "A_1") (pintype "bidirectional"))
      (node (ref "EPD_C11") (pin "1") (pinfunction "1_1") (pintype "passive"))
      (node (ref "J1") (pin "23") (pinfunction "23_23") (pintype "bidirectional"))
    )
    (net (code "39") (name "RESE") (class "Default")
      (node (ref "J1") (pin "3") (pinfunction "3_3") (pintype "bidirectional"))
      (node (ref "Q3") (pin "2") (pinfunction "S_2") (pintype "bidirectional"))
      (node (ref "R3") (pin "1") (pinfunction "1_1") (pintype "passive"))
    )
    (net (code "40") (name "RESE'") (class "Default")
      (node (ref "R2") (pin "2") (pinfunction "2_2") (pintype "passive"))
      (node (ref "R3") (pin "2") (pinfunction "2_2") (pintype "passive"))
      (node (ref "SJ1") (pin "2") (pinfunction "2_2") (pintype "passive"))
    )
    (net (code "41") (name "RESET") (class "Default")
      (node (ref "C5") (pin "1") (pinfunction "1_1") (pintype "passive"))
      (node (ref "IC1") (pin "1") (pinfunction "VOUT_1") (pintype "bidirectional"))
      (node (ref "RESET_BUTTON") (pin "3") (pinfunction "3_3") (pintype "passive"))
      (node (ref "RESET_BUTTON") (pin "4") (pinfunction "4_4") (pintype "passive"))
      (node (ref "R_RESET") (pin "2") (pinfunction "2_2") (pintype "passive"))
      (node (ref "U2") (pin "3") (pinfunction "EN_3") (pintype "input"))
    )
    (net (code "42") (name "RTC_RST") (class "Default")
      (node (ref "U2") (pin "16") (pinfunction "IO18_16") (pintype "bidirectional"))
      (node (ref "U3") (pin "4") (pinfunction "~{RST}_4") (pintype "input"))
    )
    (net (code "43") (name "RX") (class "Default")
      (node (ref "TP2") (pin "TP") (pinfunction "TP_TP") (pintype "input"))
      (node (ref "U2") (pin "24") (pinfunction "RXD0/GPIO17_24") (pintype "bidirectional"))
    )
    (net (code "44") (name "SCK") (class "Default")
      (node (ref "D10") (pin "2") (pinfunction "2_2") (pintype "passive"))
      (node (ref "J1") (pin "13") (pinfunction "13_13") (pintype "bidirectional"))
      (node (ref "J4") (pin "P5") (pinfunction "CLK_P5") (pintype "bidirectional"))
      (node (ref "R6") (pin "1") (pinfunction "1_1") (pintype "passive"))
      (node (ref "TP8") (pin "TP") (pinfunction "TP_TP") (pintype "input"))
      (node (ref "U1") (pin "6") (pinfunction "CLK_6") (pintype "input"))
      (node (ref "U2") (pin "6") (pinfunction "IO6_6") (pintype "bidirectional"))
    )
    (net (code "45") (name "SCL") (class "Default")
      (node (ref "J3") (pin "4") (pinfunction "4_4") (pintype "passive"))
      (node (ref "R2-PINH") (pin "1") (pinfunction "1_1") (pintype "passive"))
      (node (ref "SENSOR2") (pin "4") (pinfunction "SCK_4") (pintype "input"))
      (node (ref "U2") (pin "20") (pinfunction "IO22_20") (pintype "bidirectional"))
      (node (ref "U3") (pin "16") (pinfunction "SCL_16") (pintype "input"))
      (node (ref "U4") (pin "7") (pinfunction "SCL_7") (pintype "input"))
    )
    (net (code "46") (name "SDA") (class "Default")
      (node (ref "J3") (pin "3") (pinfunction "3_3") (pintype "passive"))
      (node (ref "R1_PINH") (pin "1") (pinfunction "1_1") (pintype "passive"))
      (node (ref "SENSOR2") (pin "3") (pinfunction "SDI_3") (pintype "bidirectional"))
      (node (ref "U2") (pin "19") (pinfunction "IO21_19") (pintype "bidirectional"))
      (node (ref "U3") (pin "15") (pinfunction "SDA_15") (pintype "bidirectional"))
      (node (ref "U4") (pin "8") (pinfunction "SDA_8") (pintype "bidirectional"))
    )
    (net (code "47") (name "SRC") (class "Default")
      (node (ref "C4") (pin "2") (pinfunction "2_2") (pintype "passive"))
      (node (ref "D5") (pin "1") (pinfunction "A_1") (pintype "bidirectional"))
      (node (ref "L1") (pin "1") (pinfunction "1_1") (pintype "passive"))
      (node (ref "Q3") (pin "3") (pinfunction "D_3") (pintype "bidirectional"))
    )
    (net (code "48") (name "SS_SD") (class "Default")
      (node (ref "D8") (pin "2") (pinfunction "2_2") (pintype "passive"))
      (node (ref "J4") (pin "P2") (pinfunction "CD/DAT3_P2") (pintype "bidirectional"))
      (node (ref "R10") (pin "1") (pinfunction "1_1") (pintype "passive"))
      (node (ref "U2") (pin "4") (pinfunction "IO4_4") (pintype "bidirectional"))
    )
    (net (code "49") (name "TX") (class "Default")
      (node (ref "TP1") (pin "TP") (pinfunction "TP_TP") (pintype "input"))
      (node (ref "U2") (pin "25") (pinfunction "TXD0/GPIO16_25") (pintype "bidirectional"))
    )
    (net (code "50") (name "USB_D+") (class "Default")
      (node (ref "D1") (pin "1") (pinfunction "I/O1_1_1") (pintype "bidirectional"))
      (node (ref "U2") (pin "14") (pinfunction "IO13_14") (pintype "bidirectional"))
    )
    (net (code "51") (name "USB_D-") (class "Default")
      (node (ref "D1") (pin "3") (pinfunction "I/O2_1_3") (pintype "bidirectional"))
      (node (ref "U2") (pin "13") (pinfunction "IO12_13") (pintype "bidirectional"))
    )
    (net (code "52") (name "VBAT") (class "Default")
      (node (ref "C2_BAT") (pin "1") (pinfunction "1_1") (pintype "passive"))
      (node (ref "MCP73831") (pin "3") (pinfunction "VBAT_3") (pintype "power_in"))
      (node (ref "Q1") (pin "3") (pinfunction "D_3") (pintype "bidirectional"))
      (node (ref "TP3") (pin "TP") (pinfunction "TP_TP") (pintype "input"))
      (node (ref "U4") (pin "2") (pinfunction "CELL_2") (pintype "power_in"))
      (node (ref "U4") (pin "3") (pinfunction "VDD_3") (pintype "power_in"))
    )
    (net (code "53") (name "VBUS") (class "Default")
      (node (ref "C1_BAT") (pin "1") (pinfunction "1_1") (pintype "passive"))
      (node (ref "C4_USB") (pin "1") (pinfunction "1_1") (pintype "passive"))
      (node (ref "C5_USB") (pin "1") (pinfunction "1_1") (pintype "passive"))
      (node (ref "CHG_LED") (pin "A") (pinfunction "A_A") (pintype "passive"))
      (node (ref "D1") (pin "5") (pinfunction "VBUS_5") (pintype "bidirectional"))
      (node (ref "D2") (pin "2") (pinfunction "ANODE_2") (pintype "bidirectional"))
      (node (ref "MCP73831") (pin "4") (pinfunction "VIN_4") (pintype "power_in"))
      (node (ref "PFMF.050.1") (pin "2") (pinfunction "2_2") (pintype "passive"))
      (node (ref "Q1") (pin "1") (pinfunction "G_1") (pintype "bidirectional"))
      (node (ref "R1_PWRUSB") (pin "2") (pinfunction "2_2") (pintype "passive"))
      (node (ref "TP14") (pin "TP") (pinfunction "TP_TP") (pintype "input"))
    )
    (net (code "54") (name "VRTC") (class "Default")
      (node (ref "C10_SUPERCAP") (pin "2") (pinfunction "2_2") (pintype "passive"))
      (node (ref "C8") (pin "1") (pinfunction "1_1") (pintype "passive"))
      (node (ref "R_CAPACITOR") (pin "1") (pinfunction "1_1") (pintype "passive"))
      (node (ref "U3") (pin "14") (pinfunction "VBAT_14") (pintype "power_in"))
    )
    (net (code "55") (name "VUSB") (class "Default")
      (node (ref "J2") (pin "A4") (pinfunction "A4_A4") (pintype "bidirectional"))
      (node (ref "J2") (pin "A9") (pinfunction "A9_A9") (pintype "bidirectional"))
      (node (ref "J2") (pin "B4") (pinfunction "B4_B4") (pintype "bidirectional"))
      (node (ref "J2") (pin "B9") (pinfunction "B9_B9") (pintype "bidirectional"))
      (node (ref "PFMF.050.1") (pin "1") (pinfunction "1_1") (pintype "passive"))
    )
    (net (code "56") (name "unconnected-(IC1-NC-Pad4)") (class "Default")
      (node (ref "IC1") (pin "4") (pinfunction "NC_4") (pintype "no_connect"))
    )
    (net (code "57") (name "unconnected-(IC4-NC-Pad4)") (class "Default")
      (node (ref "IC4") (pin "4") (pinfunction "NC_4") (pintype "no_connect"))
    )
    (net (code "58") (name "unconnected-(J1-Pad1)") (class "Default")
      (node (ref "J1") (pin "1") (pinfunction "1_1") (pintype "bidirectional"))
    )
    (net (code "59") (name "unconnected-(J1-Pad6)") (class "Default")
      (node (ref "J1") (pin "6") (pinfunction "6_6") (pintype "bidirectional"))
    )
    (net (code "60") (name "unconnected-(J1-Pad7)") (class "Default")
      (node (ref "J1") (pin "7") (pinfunction "7_7") (pintype "bidirectional"))
    )
    (net (code "61") (name "unconnected-(J2-PadA8)") (class "Default")
      (node (ref "J2") (pin "A8") (pinfunction "A8_A8") (pintype "bidirectional"))
    )
    (net (code "62") (name "unconnected-(J2-PadB8)") (class "Default")
      (node (ref "J2") (pin "B8") (pinfunction "B8_B8") (pintype "bidirectional"))
    )
    (net (code "63") (name "unconnected-(J4-DAT1-PadP8)") (class "Default")
      (node (ref "J4") (pin "P8") (pinfunction "DAT1_P8") (pintype "bidirectional"))
    )
    (net (code "64") (name "unconnected-(J4-DAT2-PadP1)") (class "Default")
      (node (ref "J4") (pin "P1") (pinfunction "DAT2_P1") (pintype "bidirectional"))
    )
    (net (code "65") (name "unconnected-(J4-DETECTION_1-PadS1)") (class "Default")
      (node (ref "J4") (pin "S1") (pinfunction "DETECTION_1_S1") (pintype "bidirectional"))
    )
    (net (code "66") (name "unconnected-(J4-DETECTION_2-PadS2)") (class "Default")
      (node (ref "J4") (pin "S2") (pinfunction "DETECTION_2_S2") (pintype "bidirectional"))
    )
    (net (code "67") (name "unconnected-(U2-NC-Pad22)") (class "Default")
      (node (ref "U2") (pin "22") (pinfunction "NC_22") (pintype "no_connect"))
    )
    (net (code "68") (name "unconnected-(U4-~{ALERT}-Pad5)") (class "Default")
      (node (ref "U4") (pin "5") (pinfunction "~{ALERT}_5") (pintype "output"))
    )
  )
)
